# audio_pa.net
KiCad netlist of a schematic drawn in Altium Designer
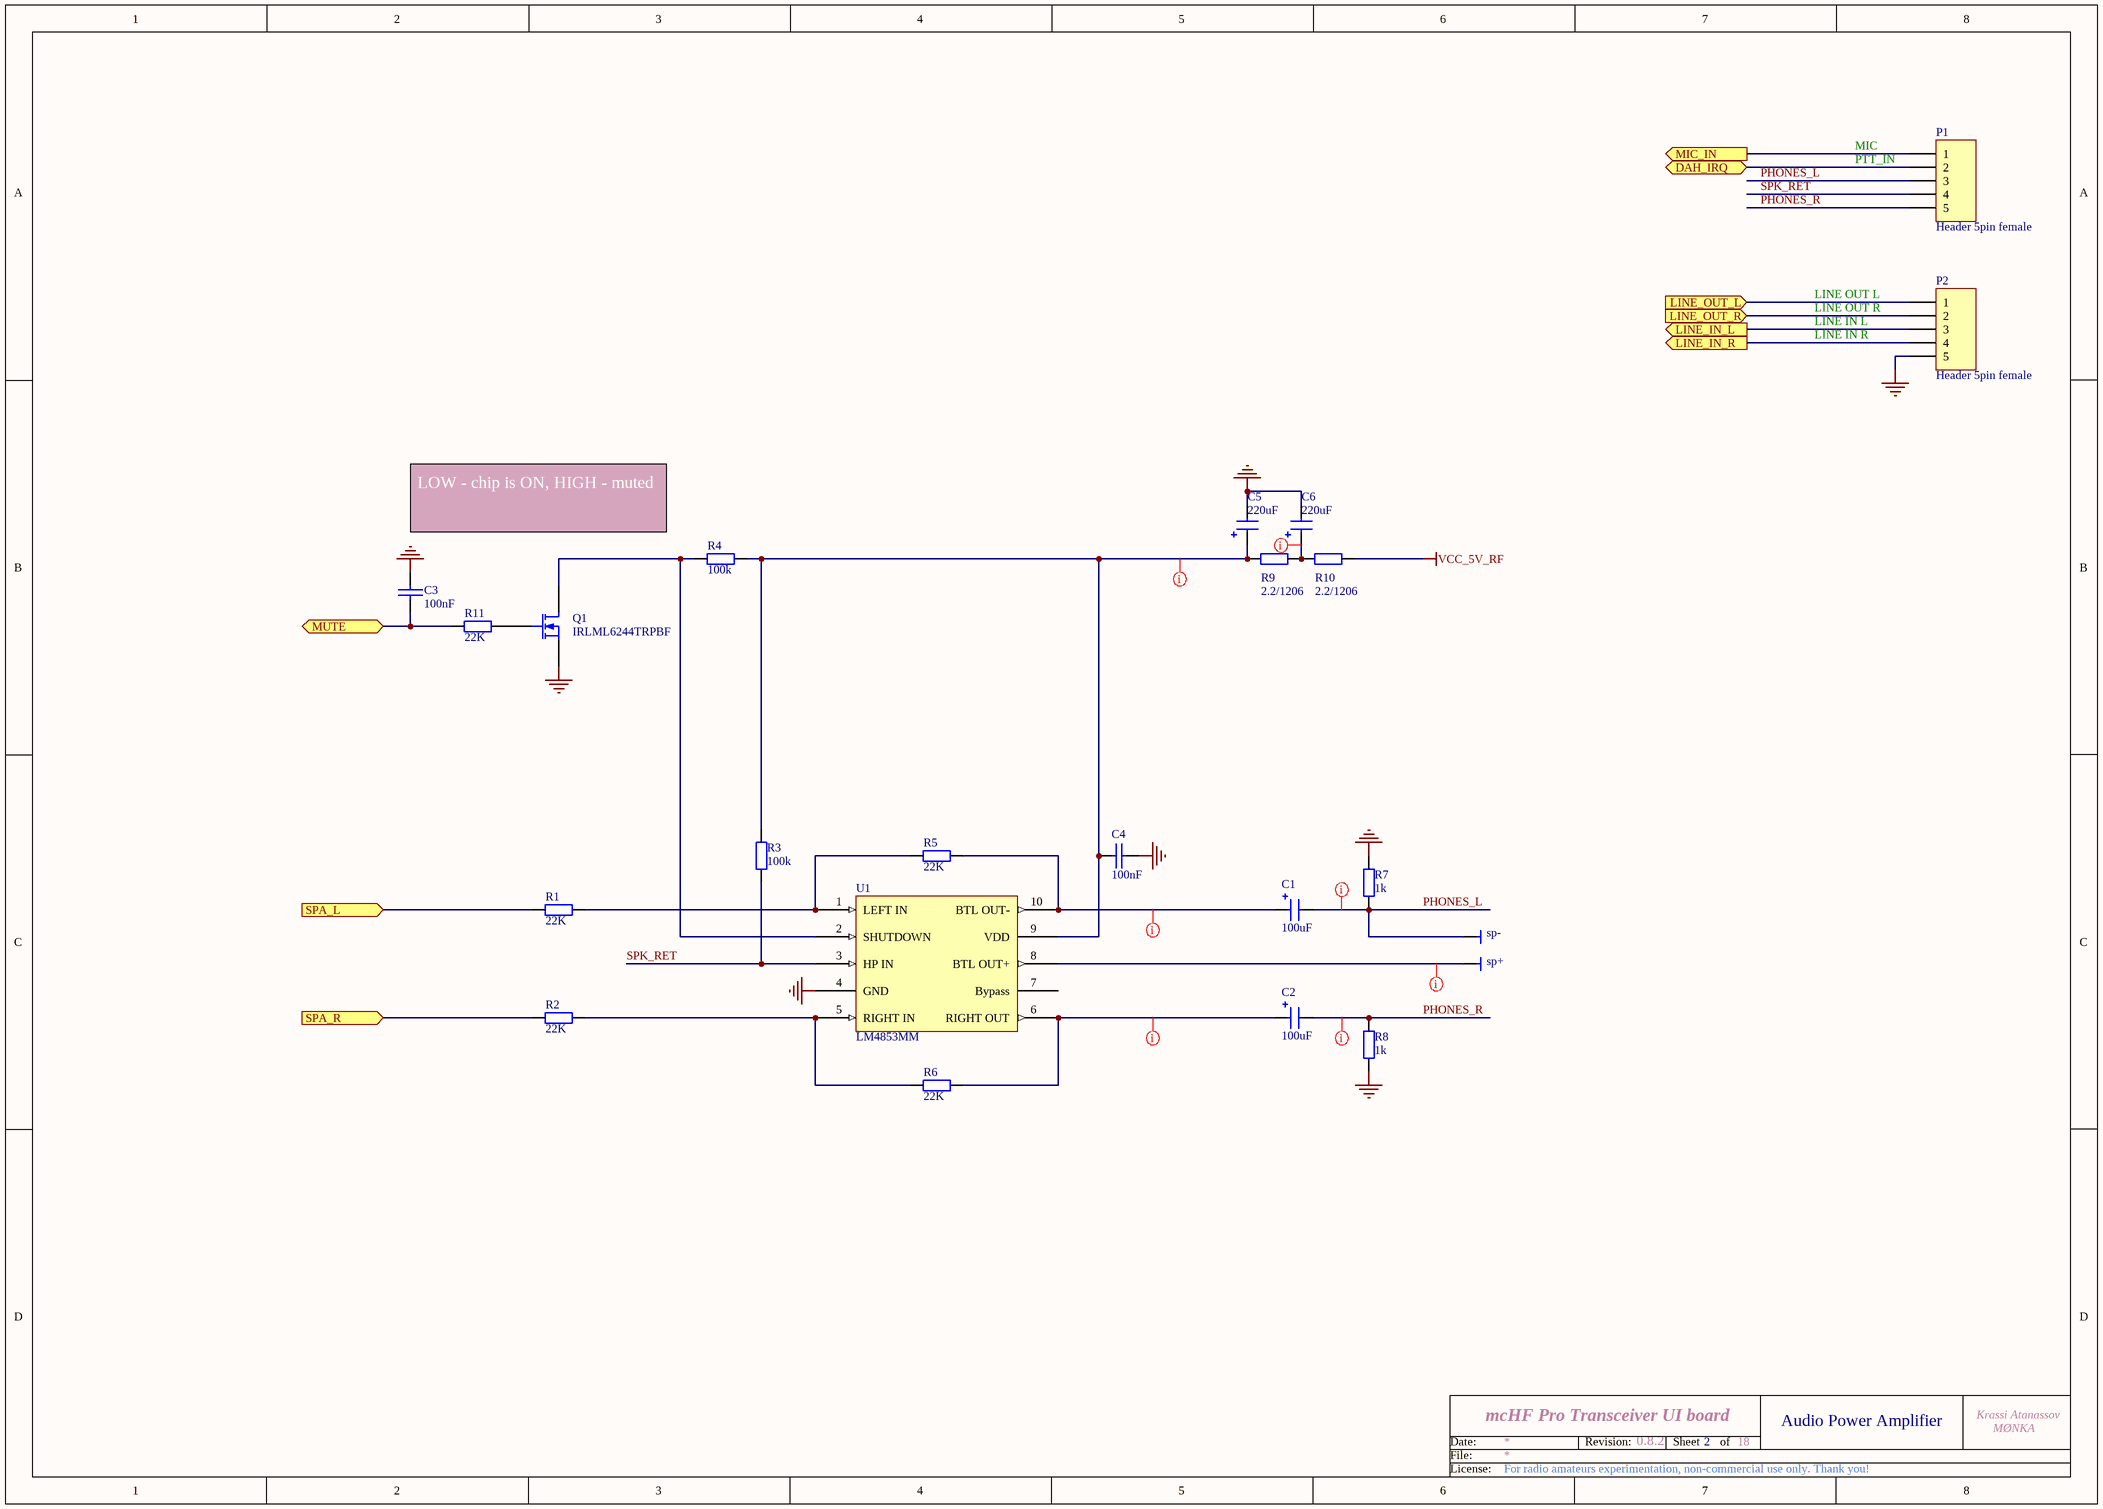
[diagram p0: audio_pa.SchDoc]

(export (version "E")
  (design (tool "Eeschema 10.0.6"))
  (components
    (comp (ref "C1")
      (value "100uF")
      (footprint "CAP_ALUM_Pro")
      (description "Electrolitic capacitor")
      (libsource (lib "mcHF_ui") (part "CAP-POL"))
    )
    (comp (ref "C2")
      (value "100uF")
      (footprint "CAP_ALUM_Pro")
      (description "Electrolitic capacitor")
      (libsource (lib "mcHF_ui") (part "CAP-POL"))
    )
    (comp (ref "C3")
      (value "100nF")
      (footprint "0805")
      (description "Capacitor")
      (libsource (lib "mcHF_ui") (part "CAP"))
    )
    (comp (ref "C4")
      (value "100nF")
      (footprint "0805")
      (description "Capacitor")
      (libsource (lib "mcHF_ui") (part "CAP"))
    )
    (comp (ref "C5")
      (value "220uF")
      (footprint "CAP_ALUM_Pro")
      (description "Electrolitic capacitor")
      (libsource (lib "mcHF_ui") (part "CAP-POL"))
    )
    (comp (ref "C6")
      (value "220uF")
      (footprint "CAP_ALUM_Pro")
      (description "Electrolitic capacitor")
      (libsource (lib "mcHF_ui") (part "CAP-POL"))
    )
    (comp (ref "P1")
      (value "Header 5pin female")
      (footprint "HDR1X5")
      (description "Header, 5-Pin")
      (libsource (lib "__ui") (part "Header 5"))
    )
    (comp (ref "P2")
      (value "Header 5pin female")
      (footprint "HDR1X5")
      (description "Header, 5-Pin")
      (libsource (lib "__ui") (part "Header 5"))
    )
    (comp (ref "Q1")
      (value "IRLML6244TRPBF")
      (footprint "SOT-23")
      (description "N-Channel MOSFET")
      (libsource (lib "mcHF_ui_b") (part "MOSFET-N"))
    )
    (comp (ref "R1")
      (value "22K")
      (footprint "0805")
      (description "Resistor")
      (libsource (lib "mcHF_ui") (part "RES"))
    )
    (comp (ref "R2")
      (value "22K")
      (footprint "0805")
      (description "Resistor")
      (libsource (lib "mcHF_ui") (part "RES"))
    )
    (comp (ref "R3")
      (value "100k")
      (footprint "0805")
      (description "Resistor")
      (libsource (lib "") (part "RES_2"))
    )
    (comp (ref "R4")
      (value "100k")
      (footprint "0805")
      (description "Resistor")
      (libsource (lib "mcHF_ui") (part "RES"))
    )
    (comp (ref "R5")
      (value "22K")
      (footprint "0805")
      (description "Resistor")
      (libsource (lib "mcHF_ui") (part "RES"))
    )
    (comp (ref "R6")
      (value "22K")
      (footprint "0805")
      (description "Resistor")
      (libsource (lib "mcHF_ui") (part "RES"))
    )
    (comp (ref "R7")
      (value "1k")
      (footprint "0805")
      (description "Resistor")
      (libsource (lib "") (part "RES_1"))
    )
    (comp (ref "R8")
      (value "1k")
      (footprint "0805")
      (description "Resistor")
      (libsource (lib "") (part "RES_1"))
    )
    (comp (ref "R9")
      (value "2.2/1206")
      (footprint "1206")
      (description "Resistor")
      (libsource (lib "mcHF_ui") (part "RES"))
    )
    (comp (ref "R10")
      (value "2.2/1206")
      (footprint "1206")
      (description "Resistor")
      (libsource (lib "mcHF_ui") (part "RES"))
    )
    (comp (ref "R11")
      (value "22K")
      (footprint "0805")
      (description "Resistor")
      (libsource (lib "mcHF_ui") (part "RES"))
    )
    (comp (ref "sp+")
      (value "TP")
      (footprint "tp_big")
      (description "Test point")
      (libsource (lib "mcHF_ui_b") (part "TP"))
    )
    (comp (ref "sp-")
      (value "TP")
      (footprint "tp_big")
      (description "Test point")
      (libsource (lib "mcHF_ui_b") (part "TP"))
    )
    (comp (ref "U1")
      (value "LM4853MM")
      (footprint "__ui:SLAB-MSOP-10_N")
      (description "Mono 1.5 W / Stereo 300mW Power Amplifier")
      (libsource (lib "__ui") (part "LM4853"))
    )
  )
  (nets
    (net (code "1") (name "/DAH_IRQ") (class "Default")
      (node (ref "P1") (pin "2") (pinfunction "2_2") (pintype "passive"))
    )
    (net (code "2") (name "/LINE_IN_L") (class "Default")
      (node (ref "P2") (pin "3") (pinfunction "3_3") (pintype "passive"))
    )
    (net (code "3") (name "/LINE_IN_R") (class "Default")
      (node (ref "P2") (pin "4") (pinfunction "4_4") (pintype "passive"))
    )
    (net (code "4") (name "/LINE_OUT_L") (class "Default")
      (node (ref "P2") (pin "1") (pinfunction "1_1") (pintype "passive"))
    )
    (net (code "5") (name "/LINE_OUT_R") (class "Default")
      (node (ref "P2") (pin "2") (pinfunction "2_2") (pintype "passive"))
    )
    (net (code "6") (name "/MIC_IN") (class "Default")
      (node (ref "P1") (pin "1") (pinfunction "1_1") (pintype "passive"))
    )
    (net (code "7") (name "/MUTE") (class "Default")
      (node (ref "C3") (pin "2") (pinfunction "2_2") (pintype "passive"))
      (node (ref "R11") (pin "2") (pinfunction "2_2") (pintype "passive"))
    )
    (net (code "8") (name "/PHONES_L") (class "Default")
      (node (ref "C1") (pin "2") (pinfunction "2_2") (pintype "passive"))
      (node (ref "P1") (pin "3") (pinfunction "3_3") (pintype "passive"))
      (node (ref "R7") (pin "1") (pinfunction "1_1") (pintype "passive"))
      (node (ref "sp-") (pin "1") (pinfunction "1_1") (pintype "passive"))
    )
    (net (code "9") (name "/PHONES_R") (class "Default")
      (node (ref "C2") (pin "2") (pinfunction "2_2") (pintype "passive"))
      (node (ref "P1") (pin "5") (pinfunction "5_5") (pintype "passive"))
      (node (ref "R8") (pin "2") (pinfunction "2_2") (pintype "passive"))
    )
    (net (code "10") (name "/SPA_L") (class "Default")
      (node (ref "R1") (pin "2") (pinfunction "2_2") (pintype "passive"))
    )
    (net (code "11") (name "/SPA_R") (class "Default")
      (node (ref "R2") (pin "2") (pinfunction "2_2") (pintype "passive"))
    )
    (net (code "12") (name "/SPK_RET") (class "Default")
      (node (ref "P1") (pin "4") (pinfunction "4_4") (pintype "passive"))
      (node (ref "R3") (pin "2") (pinfunction "2_2") (pintype "passive"))
      (node (ref "U1") (pin "3") (pinfunction "HP_IN_3") (pintype "input"))
    )
    (net (code "13") (name "GND") (class "Default")
      (node (ref "C3") (pin "1") (pinfunction "1_1") (pintype "passive"))
      (node (ref "C4") (pin "1") (pinfunction "1_1") (pintype "passive"))
      (node (ref "C5") (pin "2") (pinfunction "2_2") (pintype "passive"))
      (node (ref "C6") (pin "2") (pinfunction "2_2") (pintype "passive"))
      (node (ref "P2") (pin "5") (pinfunction "5_5") (pintype "passive"))
      (node (ref "Q1") (pin "2") (pinfunction "S_2") (pintype "passive"))
      (node (ref "R7") (pin "2") (pinfunction "2_2") (pintype "passive"))
      (node (ref "R8") (pin "1") (pinfunction "1_1") (pintype "passive"))
      (node (ref "U1") (pin "4") (pinfunction "GND_4") (pintype "power_in"))
    )
    (net (code "14") (name "Net-(C6-Pad1)") (class "Default")
      (node (ref "C6") (pin "1") (pinfunction "1_1") (pintype "passive"))
      (node (ref "R10") (pin "2") (pinfunction "2_2") (pintype "passive"))
      (node (ref "R9") (pin "1") (pinfunction "1_1") (pintype "passive"))
    )
    (net (code "15") (name "Net-(Q1-D)") (class "Default")
      (node (ref "Q1") (pin "3") (pinfunction "D_3") (pintype "passive"))
      (node (ref "R4") (pin "2") (pinfunction "2_2") (pintype "passive"))
      (node (ref "U1") (pin "2") (pinfunction "SHUTDOWN_2") (pintype "input"))
    )
    (net (code "16") (name "Net-(Q1-G)") (class "Default")
      (node (ref "Q1") (pin "1") (pinfunction "G_1") (pintype "passive"))
      (node (ref "R11") (pin "1") (pinfunction "1_1") (pintype "passive"))
    )
    (net (code "17") (name "Net-(U1-BTL_OUT+)") (class "Default")
      (node (ref "U1") (pin "8") (pinfunction "BTL_OUT+_8") (pintype "output"))
      (node (ref "sp+") (pin "1") (pinfunction "1_1") (pintype "passive"))
    )
    (net (code "18") (name "Net-(U1-BTL_OUT-)") (class "Default")
      (node (ref "C1") (pin "1") (pinfunction "1_1") (pintype "passive"))
      (node (ref "R5") (pin "1") (pinfunction "1_1") (pintype "passive"))
      (node (ref "U1") (pin "10") (pinfunction "BTL_OUT-_10") (pintype "output"))
    )
    (net (code "19") (name "Net-(U1-LEFT_IN)") (class "Default")
      (node (ref "R1") (pin "1") (pinfunction "1_1") (pintype "passive"))
      (node (ref "R5") (pin "2") (pinfunction "2_2") (pintype "passive"))
      (node (ref "U1") (pin "1") (pinfunction "LEFT_IN_1") (pintype "input"))
    )
    (net (code "20") (name "Net-(U1-RIGHT_IN)") (class "Default")
      (node (ref "R2") (pin "1") (pinfunction "1_1") (pintype "passive"))
      (node (ref "R6") (pin "2") (pinfunction "2_2") (pintype "passive"))
      (node (ref "U1") (pin "5") (pinfunction "RIGHT_IN_5") (pintype "input"))
    )
    (net (code "21") (name "Net-(U1-RIGHT_OUT)") (class "Default")
      (node (ref "C2") (pin "1") (pinfunction "1_1") (pintype "passive"))
      (node (ref "R6") (pin "1") (pinfunction "1_1") (pintype "passive"))
      (node (ref "U1") (pin "6") (pinfunction "RIGHT_OUT_6") (pintype "output"))
    )
    (net (code "22") (name "Net-(U1-VDD)") (class "Default")
      (node (ref "C4") (pin "2") (pinfunction "2_2") (pintype "passive"))
      (node (ref "C5") (pin "1") (pinfunction "1_1") (pintype "passive"))
      (node (ref "R3") (pin "1") (pinfunction "1_1") (pintype "passive"))
      (node (ref "R4") (pin "1") (pinfunction "1_1") (pintype "passive"))
      (node (ref "R9") (pin "2") (pinfunction "2_2") (pintype "passive"))
      (node (ref "U1") (pin "9") (pinfunction "VDD_9") (pintype "passive"))
    )
    (net (code "23") (name "VCC_5V_RF") (class "Default")
      (node (ref "R10") (pin "1") (pinfunction "1_1") (pintype "passive"))
    )
    (net (code "24") (name "unconnected-(U1-Bypass-Pad7)") (class "Default")
      (node (ref "U1") (pin "7") (pinfunction "Bypass_7") (pintype "passive"))
    )
  )
)
